# Middle_SEU.net
KiCad netlist of a schematic drawn in Altium Designer
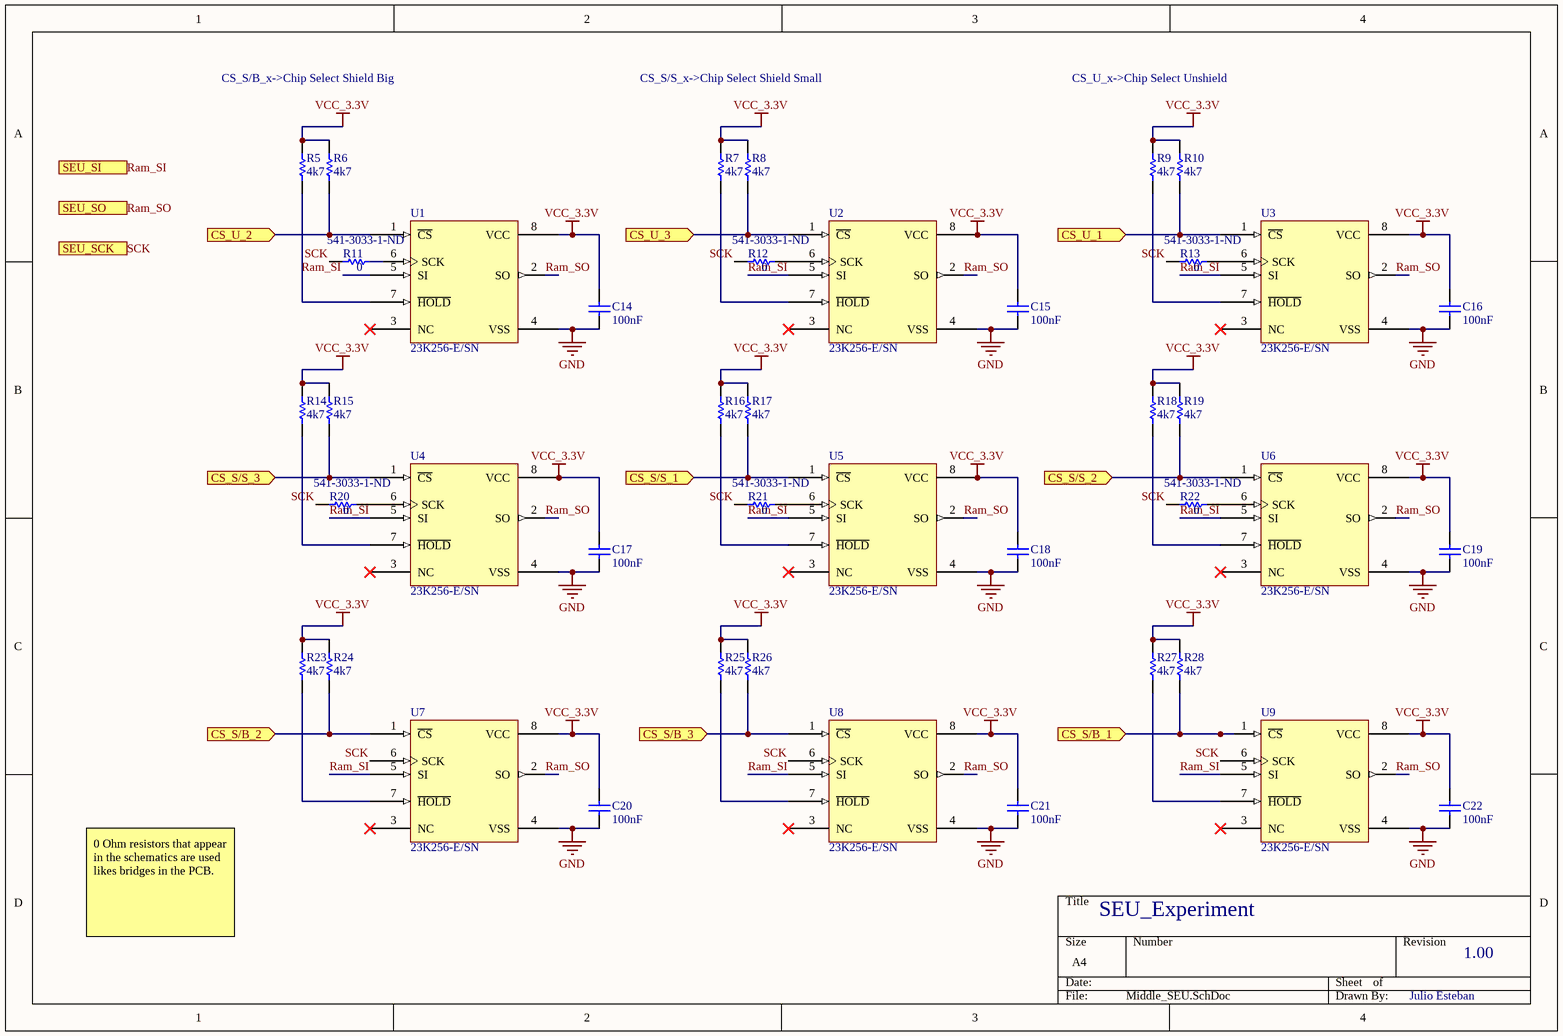
[diagram p0: Middle_SEU.SchDoc]

(export (version "E")
  (design (tool "Eeschema 10.0.6"))
  (components
    (comp (ref "C14")
      (value "100nF")
      (footprint "C1206")
      (description "1206 Capacitor")
      (libsource (lib "Middle_Symbols") (part "C1206"))
    )
    (comp (ref "C15")
      (value "100nF")
      (footprint "C1206")
      (description "1206 Capacitor")
      (libsource (lib "Middle_Symbols") (part "C1206"))
    )
    (comp (ref "C16")
      (value "100nF")
      (footprint "C1206")
      (description "1206 Capacitor")
      (libsource (lib "Middle_Symbols") (part "C1206"))
    )
    (comp (ref "C17")
      (value "100nF")
      (footprint "C1206")
      (description "1206 Capacitor")
      (libsource (lib "Middle_Symbols") (part "C1206"))
    )
    (comp (ref "C18")
      (value "100nF")
      (footprint "C1206")
      (description "1206 Capacitor")
      (libsource (lib "Middle_Symbols") (part "C1206"))
    )
    (comp (ref "C19")
      (value "100nF")
      (footprint "C1206")
      (description "1206 Capacitor")
      (libsource (lib "Middle_Symbols") (part "C1206"))
    )
    (comp (ref "C20")
      (value "100nF")
      (footprint "C1206")
      (description "1206 Capacitor")
      (libsource (lib "Middle_Symbols") (part "C1206"))
    )
    (comp (ref "C21")
      (value "100nF")
      (footprint "C1206")
      (description "1206 Capacitor")
      (libsource (lib "Middle_Symbols") (part "C1206"))
    )
    (comp (ref "C22")
      (value "100nF")
      (footprint "C1206")
      (description "1206 Capacitor")
      (libsource (lib "Middle_Symbols") (part "C1206"))
    )
    (comp (ref "R5")
      (value "4k7")
      (footprint "R1206")
      (description "1206 Resistor")
      (libsource (lib "Middle_Symbols") (part "R1206"))
    )
    (comp (ref "R6")
      (value "4k7")
      (footprint "R1206")
      (description "1206 Resistor")
      (libsource (lib "Middle_Symbols") (part "R1206"))
    )
    (comp (ref "R7")
      (value "4k7")
      (footprint "R1206")
      (description "1206 Resistor")
      (libsource (lib "Middle_Symbols") (part "R1206"))
    )
    (comp (ref "R8")
      (value "4k7")
      (footprint "R1206")
      (description "1206 Resistor")
      (libsource (lib "Middle_Symbols") (part "R1206"))
    )
    (comp (ref "R9")
      (value "4k7")
      (footprint "R1206")
      (description "1206 Resistor")
      (libsource (lib "Middle_Symbols") (part "R1206"))
    )
    (comp (ref "R10")
      (value "4k7")
      (footprint "R1206")
      (description "1206 Resistor")
      (libsource (lib "Middle_Symbols") (part "R1206"))
    )
    (comp (ref "R11")
      (value "0")
      (footprint "R1206")
      (description "1206 Resistor")
      (fields (field (name "SUPPLIER PART NUMBER 1") "541-3033-1-ND"))
      (libsource (lib "Middle_Symbols") (part "R1206"))
    )
    (comp (ref "R12")
      (value "0")
      (footprint "R1206")
      (description "1206 Resistor")
      (fields (field (name "SUPPLIER PART NUMBER 1") "541-3033-1-ND"))
      (libsource (lib "Middle_Symbols") (part "R1206"))
    )
    (comp (ref "R13")
      (value "0")
      (footprint "R1206")
      (description "1206 Resistor")
      (fields (field (name "SUPPLIER PART NUMBER 1") "541-3033-1-ND"))
      (libsource (lib "Middle_Symbols") (part "R1206"))
    )
    (comp (ref "R14")
      (value "4k7")
      (footprint "R1206")
      (description "1206 Resistor")
      (libsource (lib "Middle_Symbols") (part "R1206"))
    )
    (comp (ref "R15")
      (value "4k7")
      (footprint "R1206")
      (description "1206 Resistor")
      (libsource (lib "Middle_Symbols") (part "R1206"))
    )
    (comp (ref "R16")
      (value "4k7")
      (footprint "R1206")
      (description "1206 Resistor")
      (libsource (lib "Middle_Symbols") (part "R1206"))
    )
    (comp (ref "R17")
      (value "4k7")
      (footprint "R1206")
      (description "1206 Resistor")
      (libsource (lib "Middle_Symbols") (part "R1206"))
    )
    (comp (ref "R18")
      (value "4k7")
      (footprint "R1206")
      (description "1206 Resistor")
      (libsource (lib "Middle_Symbols") (part "R1206"))
    )
    (comp (ref "R19")
      (value "4k7")
      (footprint "R1206")
      (description "1206 Resistor")
      (libsource (lib "Middle_Symbols") (part "R1206"))
    )
    (comp (ref "R20")
      (value "0")
      (footprint "R1206")
      (description "1206 Resistor")
      (fields (field (name "SUPPLIER PART NUMBER 1") "541-3033-1-ND"))
      (libsource (lib "Middle_Symbols") (part "R1206"))
    )
    (comp (ref "R21")
      (value "0")
      (footprint "R1206")
      (description "1206 Resistor")
      (fields (field (name "SUPPLIER PART NUMBER 1") "541-3033-1-ND"))
      (libsource (lib "Middle_Symbols") (part "R1206"))
    )
    (comp (ref "R22")
      (value "0")
      (footprint "R1206")
      (description "1206 Resistor")
      (fields (field (name "SUPPLIER PART NUMBER 1") "541-3033-1-ND"))
      (libsource (lib "Middle_Symbols") (part "R1206"))
    )
    (comp (ref "R23")
      (value "4k7")
      (footprint "R1206")
      (description "1206 Resistor")
      (libsource (lib "Middle_Symbols") (part "R1206"))
    )
    (comp (ref "R24")
      (value "4k7")
      (footprint "R1206")
      (description "1206 Resistor")
      (libsource (lib "Middle_Symbols") (part "R1206"))
    )
    (comp (ref "R25")
      (value "4k7")
      (footprint "R1206")
      (description "1206 Resistor")
      (libsource (lib "Middle_Symbols") (part "R1206"))
    )
    (comp (ref "R26")
      (value "4k7")
      (footprint "R1206")
      (description "1206 Resistor")
      (libsource (lib "Middle_Symbols") (part "R1206"))
    )
    (comp (ref "R27")
      (value "4k7")
      (footprint "R1206")
      (description "1206 Resistor")
      (libsource (lib "Middle_Symbols") (part "R1206"))
    )
    (comp (ref "R28")
      (value "4k7")
      (footprint "R1206")
      (description "1206 Resistor")
      (libsource (lib "Middle_Symbols") (part "R1206"))
    )
    (comp (ref "U1")
      (value "23K256-E/SN")
      (footprint "SOIC-SN8_L")
      (description "256K, 32768x8-bit, 3.6V SPI Serial SRAM, 8-Pin SOIC 3.9mm, Extended Temperature")
      (fields (field (name "MANUFACTURER") "Microchip"))
      (libsource (lib "Schlib1") (part "23K256-E/SN"))
    )
    (comp (ref "U2")
      (value "23K256-E/SN")
      (footprint "SOIC-SN8_L")
      (description "256K, 32768x8-bit, 3.6V SPI Serial SRAM, 8-Pin SOIC 3.9mm, Extended Temperature")
      (fields (field (name "MANUFACTURER") "Microchip"))
      (libsource (lib "Schlib1") (part "23K256-E/SN"))
    )
    (comp (ref "U3")
      (value "23K256-E/SN")
      (footprint "SOIC-SN8_L")
      (description "256K, 32768x8-bit, 3.6V SPI Serial SRAM, 8-Pin SOIC 3.9mm, Extended Temperature")
      (fields (field (name "MANUFACTURER") "Microchip"))
      (libsource (lib "Schlib1") (part "23K256-E/SN"))
    )
    (comp (ref "U4")
      (value "23K256-E/SN")
      (footprint "SOIC-SN8_L")
      (description "256K, 32768x8-bit, 3.6V SPI Serial SRAM, 8-Pin SOIC 3.9mm, Extended Temperature")
      (fields (field (name "MANUFACTURER") "Microchip"))
      (libsource (lib "Schlib1") (part "23K256-E/SN"))
    )
    (comp (ref "U5")
      (value "23K256-E/SN")
      (footprint "SOIC-SN8_L")
      (description "256K, 32768x8-bit, 3.6V SPI Serial SRAM, 8-Pin SOIC 3.9mm, Extended Temperature")
      (fields (field (name "MANUFACTURER") "Microchip"))
      (libsource (lib "Schlib1") (part "23K256-E/SN"))
    )
    (comp (ref "U6")
      (value "23K256-E/SN")
      (footprint "SOIC-SN8_L")
      (description "256K, 32768x8-bit, 3.6V SPI Serial SRAM, 8-Pin SOIC 3.9mm, Extended Temperature")
      (fields (field (name "MANUFACTURER") "Microchip"))
      (libsource (lib "Schlib1") (part "23K256-E/SN"))
    )
    (comp (ref "U7")
      (value "23K256-E/SN")
      (footprint "SOIC-SN8_L")
      (description "256K, 32768x8-bit, 3.6V SPI Serial SRAM, 8-Pin SOIC 3.9mm, Extended Temperature")
      (fields (field (name "MANUFACTURER") "Microchip"))
      (libsource (lib "Schlib1") (part "23K256-E/SN"))
    )
    (comp (ref "U8")
      (value "23K256-E/SN")
      (footprint "SOIC-SN8_L")
      (description "256K, 32768x8-bit, 3.6V SPI Serial SRAM, 8-Pin SOIC 3.9mm, Extended Temperature")
      (fields (field (name "MANUFACTURER") "Microchip"))
      (libsource (lib "Schlib1") (part "23K256-E/SN"))
    )
    (comp (ref "U9")
      (value "23K256-E/SN")
      (footprint "SOIC-SN8_L")
      (description "256K, 32768x8-bit, 3.6V SPI Serial SRAM, 8-Pin SOIC 3.9mm, Extended Temperature")
      (fields (field (name "MANUFACTURER") "Microchip"))
      (libsource (lib "Schlib1") (part "23K256-E/SN"))
    )
  )
  (nets
    (net (code "1") (name "/CS_S{slash}B_1") (class "Default")
      (node (ref "R28") (pin "1") (pinfunction "1_1") (pintype "passive"))
      (node (ref "U9") (pin "1") (pinfunction "~{CS}_1") (pintype "input"))
    )
    (net (code "2") (name "/CS_S{slash}B_2") (class "Default")
      (node (ref "R24") (pin "1") (pinfunction "1_1") (pintype "passive"))
      (node (ref "U7") (pin "1") (pinfunction "~{CS}_1") (pintype "input"))
    )
    (net (code "3") (name "/CS_S{slash}B_3") (class "Default")
      (node (ref "R26") (pin "1") (pinfunction "1_1") (pintype "passive"))
      (node (ref "U8") (pin "1") (pinfunction "~{CS}_1") (pintype "input"))
    )
    (net (code "4") (name "/CS_S{slash}S_1") (class "Default")
      (node (ref "R17") (pin "1") (pinfunction "1_1") (pintype "passive"))
      (node (ref "U5") (pin "1") (pinfunction "~{CS}_1") (pintype "input"))
    )
    (net (code "5") (name "/CS_S{slash}S_2") (class "Default")
      (node (ref "R19") (pin "1") (pinfunction "1_1") (pintype "passive"))
      (node (ref "U6") (pin "1") (pinfunction "~{CS}_1") (pintype "input"))
    )
    (net (code "6") (name "/CS_S{slash}S_3") (class "Default")
      (node (ref "R15") (pin "1") (pinfunction "1_1") (pintype "passive"))
      (node (ref "U4") (pin "1") (pinfunction "~{CS}_1") (pintype "input"))
    )
    (net (code "7") (name "/CS_U_1") (class "Default")
      (node (ref "R10") (pin "1") (pinfunction "1_1") (pintype "passive"))
      (node (ref "U3") (pin "1") (pinfunction "~{CS}_1") (pintype "input"))
    )
    (net (code "8") (name "/CS_U_2") (class "Default")
      (node (ref "R6") (pin "1") (pinfunction "1_1") (pintype "passive"))
      (node (ref "U1") (pin "1") (pinfunction "~{CS}_1") (pintype "input"))
    )
    (net (code "9") (name "/CS_U_3") (class "Default")
      (node (ref "R8") (pin "1") (pinfunction "1_1") (pintype "passive"))
      (node (ref "U2") (pin "1") (pinfunction "~{CS}_1") (pintype "input"))
    )
    (net (code "10") (name "/Ram_SI") (class "Default")
      (node (ref "U1") (pin "5") (pinfunction "SI_5") (pintype "input"))
      (node (ref "U2") (pin "5") (pinfunction "SI_5") (pintype "input"))
      (node (ref "U3") (pin "5") (pinfunction "SI_5") (pintype "input"))
      (node (ref "U4") (pin "5") (pinfunction "SI_5") (pintype "input"))
      (node (ref "U5") (pin "5") (pinfunction "SI_5") (pintype "input"))
      (node (ref "U6") (pin "5") (pinfunction "SI_5") (pintype "input"))
      (node (ref "U7") (pin "5") (pinfunction "SI_5") (pintype "input"))
      (node (ref "U8") (pin "5") (pinfunction "SI_5") (pintype "input"))
      (node (ref "U9") (pin "5") (pinfunction "SI_5") (pintype "input"))
    )
    (net (code "11") (name "/Ram_SO") (class "Default")
      (node (ref "U1") (pin "2") (pinfunction "SO_2") (pintype "output"))
      (node (ref "U2") (pin "2") (pinfunction "SO_2") (pintype "output"))
      (node (ref "U3") (pin "2") (pinfunction "SO_2") (pintype "output"))
      (node (ref "U4") (pin "2") (pinfunction "SO_2") (pintype "output"))
      (node (ref "U5") (pin "2") (pinfunction "SO_2") (pintype "output"))
      (node (ref "U6") (pin "2") (pinfunction "SO_2") (pintype "output"))
      (node (ref "U7") (pin "2") (pinfunction "SO_2") (pintype "output"))
      (node (ref "U8") (pin "2") (pinfunction "SO_2") (pintype "output"))
      (node (ref "U9") (pin "2") (pinfunction "SO_2") (pintype "output"))
    )
    (net (code "12") (name "/SCK") (class "Default")
      (node (ref "R11") (pin "2") (pinfunction "2_2") (pintype "passive"))
      (node (ref "R12") (pin "2") (pinfunction "2_2") (pintype "passive"))
      (node (ref "R13") (pin "2") (pinfunction "2_2") (pintype "passive"))
      (node (ref "R20") (pin "2") (pinfunction "2_2") (pintype "passive"))
      (node (ref "R21") (pin "2") (pinfunction "2_2") (pintype "passive"))
      (node (ref "R22") (pin "2") (pinfunction "2_2") (pintype "passive"))
      (node (ref "U7") (pin "6") (pinfunction "SCK_6") (pintype "input"))
      (node (ref "U8") (pin "6") (pinfunction "SCK_6") (pintype "input"))
      (node (ref "U9") (pin "6") (pinfunction "SCK_6") (pintype "input"))
    )
    (net (code "13") (name "GND") (class "Default")
      (node (ref "C14") (pin "1") (pinfunction "1_1") (pintype "passive"))
      (node (ref "C15") (pin "1") (pinfunction "1_1") (pintype "passive"))
      (node (ref "C16") (pin "1") (pinfunction "1_1") (pintype "passive"))
      (node (ref "C17") (pin "1") (pinfunction "1_1") (pintype "passive"))
      (node (ref "C18") (pin "1") (pinfunction "1_1") (pintype "passive"))
      (node (ref "C19") (pin "1") (pinfunction "1_1") (pintype "passive"))
      (node (ref "C20") (pin "1") (pinfunction "1_1") (pintype "passive"))
      (node (ref "C21") (pin "1") (pinfunction "1_1") (pintype "passive"))
      (node (ref "C22") (pin "1") (pinfunction "1_1") (pintype "passive"))
      (node (ref "U1") (pin "4") (pinfunction "VSS_4") (pintype "power_in"))
      (node (ref "U2") (pin "4") (pinfunction "VSS_4") (pintype "power_in"))
      (node (ref "U3") (pin "4") (pinfunction "VSS_4") (pintype "power_in"))
      (node (ref "U4") (pin "4") (pinfunction "VSS_4") (pintype "power_in"))
      (node (ref "U5") (pin "4") (pinfunction "VSS_4") (pintype "power_in"))
      (node (ref "U6") (pin "4") (pinfunction "VSS_4") (pintype "power_in"))
      (node (ref "U7") (pin "4") (pinfunction "VSS_4") (pintype "power_in"))
      (node (ref "U8") (pin "4") (pinfunction "VSS_4") (pintype "power_in"))
      (node (ref "U9") (pin "4") (pinfunction "VSS_4") (pintype "power_in"))
    )
    (net (code "14") (name "Net-(U1-SCK)") (class "Default")
      (node (ref "R11") (pin "1") (pinfunction "1_1") (pintype "passive"))
      (node (ref "U1") (pin "6") (pinfunction "SCK_6") (pintype "input"))
    )
    (net (code "15") (name "Net-(U1-~{HOLD})") (class "Default")
      (node (ref "R5") (pin "1") (pinfunction "1_1") (pintype "passive"))
      (node (ref "U1") (pin "7") (pinfunction "~{HOLD}_7") (pintype "input"))
    )
    (net (code "16") (name "Net-(U2-SCK)") (class "Default")
      (node (ref "R12") (pin "1") (pinfunction "1_1") (pintype "passive"))
      (node (ref "U2") (pin "6") (pinfunction "SCK_6") (pintype "input"))
    )
    (net (code "17") (name "Net-(U2-~{HOLD})") (class "Default")
      (node (ref "R7") (pin "1") (pinfunction "1_1") (pintype "passive"))
      (node (ref "U2") (pin "7") (pinfunction "~{HOLD}_7") (pintype "input"))
    )
    (net (code "18") (name "Net-(U3-SCK)") (class "Default")
      (node (ref "R13") (pin "1") (pinfunction "1_1") (pintype "passive"))
      (node (ref "U3") (pin "6") (pinfunction "SCK_6") (pintype "input"))
    )
    (net (code "19") (name "Net-(U3-~{HOLD})") (class "Default")
      (node (ref "R9") (pin "1") (pinfunction "1_1") (pintype "passive"))
      (node (ref "U3") (pin "7") (pinfunction "~{HOLD}_7") (pintype "input"))
    )
    (net (code "20") (name "Net-(U4-SCK)") (class "Default")
      (node (ref "R20") (pin "1") (pinfunction "1_1") (pintype "passive"))
      (node (ref "U4") (pin "6") (pinfunction "SCK_6") (pintype "input"))
    )
    (net (code "21") (name "Net-(U4-~{HOLD})") (class "Default")
      (node (ref "R14") (pin "1") (pinfunction "1_1") (pintype "passive"))
      (node (ref "U4") (pin "7") (pinfunction "~{HOLD}_7") (pintype "input"))
    )
    (net (code "22") (name "Net-(U5-SCK)") (class "Default")
      (node (ref "R21") (pin "1") (pinfunction "1_1") (pintype "passive"))
      (node (ref "U5") (pin "6") (pinfunction "SCK_6") (pintype "input"))
    )
    (net (code "23") (name "Net-(U5-~{HOLD})") (class "Default")
      (node (ref "R16") (pin "1") (pinfunction "1_1") (pintype "passive"))
      (node (ref "U5") (pin "7") (pinfunction "~{HOLD}_7") (pintype "input"))
    )
    (net (code "24") (name "Net-(U6-SCK)") (class "Default")
      (node (ref "R22") (pin "1") (pinfunction "1_1") (pintype "passive"))
      (node (ref "U6") (pin "6") (pinfunction "SCK_6") (pintype "input"))
    )
    (net (code "25") (name "Net-(U6-~{HOLD})") (class "Default")
      (node (ref "R18") (pin "1") (pinfunction "1_1") (pintype "passive"))
      (node (ref "U6") (pin "7") (pinfunction "~{HOLD}_7") (pintype "input"))
    )
    (net (code "26") (name "Net-(U7-~{HOLD})") (class "Default")
      (node (ref "R23") (pin "1") (pinfunction "1_1") (pintype "passive"))
      (node (ref "U7") (pin "7") (pinfunction "~{HOLD}_7") (pintype "input"))
    )
    (net (code "27") (name "Net-(U8-~{HOLD})") (class "Default")
      (node (ref "R25") (pin "1") (pinfunction "1_1") (pintype "passive"))
      (node (ref "U8") (pin "7") (pinfunction "~{HOLD}_7") (pintype "input"))
    )
    (net (code "28") (name "Net-(U9-~{HOLD})") (class "Default")
      (node (ref "R27") (pin "1") (pinfunction "1_1") (pintype "passive"))
      (node (ref "U9") (pin "7") (pinfunction "~{HOLD}_7") (pintype "input"))
    )
    (net (code "29") (name "VCC_3.3V") (class "Default")
      (node (ref "C14") (pin "2") (pinfunction "2_2") (pintype "passive"))
      (node (ref "C15") (pin "2") (pinfunction "2_2") (pintype "passive"))
      (node (ref "C16") (pin "2") (pinfunction "2_2") (pintype "passive"))
      (node (ref "C17") (pin "2") (pinfunction "2_2") (pintype "passive"))
      (node (ref "C18") (pin "2") (pinfunction "2_2") (pintype "passive"))
      (node (ref "C19") (pin "2") (pinfunction "2_2") (pintype "passive"))
      (node (ref "C20") (pin "2") (pinfunction "2_2") (pintype "passive"))
      (node (ref "C21") (pin "2") (pinfunction "2_2") (pintype "passive"))
      (node (ref "C22") (pin "2") (pinfunction "2_2") (pintype "passive"))
      (node (ref "R10") (pin "2") (pinfunction "2_2") (pintype "passive"))
      (node (ref "R14") (pin "2") (pinfunction "2_2") (pintype "passive"))
      (node (ref "R15") (pin "2") (pinfunction "2_2") (pintype "passive"))
      (node (ref "R16") (pin "2") (pinfunction "2_2") (pintype "passive"))
      (node (ref "R17") (pin "2") (pinfunction "2_2") (pintype "passive"))
      (node (ref "R18") (pin "2") (pinfunction "2_2") (pintype "passive"))
      (node (ref "R19") (pin "2") (pinfunction "2_2") (pintype "passive"))
      (node (ref "R23") (pin "2") (pinfunction "2_2") (pintype "passive"))
      (node (ref "R24") (pin "2") (pinfunction "2_2") (pintype "passive"))
      (node (ref "R25") (pin "2") (pinfunction "2_2") (pintype "passive"))
      (node (ref "R26") (pin "2") (pinfunction "2_2") (pintype "passive"))
      (node (ref "R27") (pin "2") (pinfunction "2_2") (pintype "passive"))
      (node (ref "R28") (pin "2") (pinfunction "2_2") (pintype "passive"))
      (node (ref "R5") (pin "2") (pinfunction "2_2") (pintype "passive"))
      (node (ref "R6") (pin "2") (pinfunction "2_2") (pintype "passive"))
      (node (ref "R7") (pin "2") (pinfunction "2_2") (pintype "passive"))
      (node (ref "R8") (pin "2") (pinfunction "2_2") (pintype "passive"))
      (node (ref "R9") (pin "2") (pinfunction "2_2") (pintype "passive"))
      (node (ref "U1") (pin "8") (pinfunction "VCC_8") (pintype "power_in"))
      (node (ref "U2") (pin "8") (pinfunction "VCC_8") (pintype "power_in"))
      (node (ref "U3") (pin "8") (pinfunction "VCC_8") (pintype "power_in"))
      (node (ref "U4") (pin "8") (pinfunction "VCC_8") (pintype "power_in"))
      (node (ref "U5") (pin "8") (pinfunction "VCC_8") (pintype "power_in"))
      (node (ref "U6") (pin "8") (pinfunction "VCC_8") (pintype "power_in"))
      (node (ref "U7") (pin "8") (pinfunction "VCC_8") (pintype "power_in"))
      (node (ref "U8") (pin "8") (pinfunction "VCC_8") (pintype "power_in"))
      (node (ref "U9") (pin "8") (pinfunction "VCC_8") (pintype "power_in"))
    )
    (net (code "30") (name "unconnected-(U1-NC-Pad3)") (class "Default")
      (node (ref "U1") (pin "3") (pinfunction "NC_3") (pintype "passive+no_connect"))
    )
    (net (code "31") (name "unconnected-(U2-NC-Pad3)") (class "Default")
      (node (ref "U2") (pin "3") (pinfunction "NC_3") (pintype "passive+no_connect"))
    )
    (net (code "32") (name "unconnected-(U3-NC-Pad3)") (class "Default")
      (node (ref "U3") (pin "3") (pinfunction "NC_3") (pintype "passive+no_connect"))
    )
    (net (code "33") (name "unconnected-(U4-NC-Pad3)") (class "Default")
      (node (ref "U4") (pin "3") (pinfunction "NC_3") (pintype "passive+no_connect"))
    )
    (net (code "34") (name "unconnected-(U5-NC-Pad3)") (class "Default")
      (node (ref "U5") (pin "3") (pinfunction "NC_3") (pintype "passive+no_connect"))
    )
    (net (code "35") (name "unconnected-(U6-NC-Pad3)") (class "Default")
      (node (ref "U6") (pin "3") (pinfunction "NC_3") (pintype "passive+no_connect"))
    )
    (net (code "36") (name "unconnected-(U7-NC-Pad3)") (class "Default")
      (node (ref "U7") (pin "3") (pinfunction "NC_3") (pintype "passive+no_connect"))
    )
    (net (code "37") (name "unconnected-(U8-NC-Pad3)") (class "Default")
      (node (ref "U8") (pin "3") (pinfunction "NC_3") (pintype "passive+no_connect"))
    )
    (net (code "38") (name "unconnected-(U9-NC-Pad3)") (class "Default")
      (node (ref "U9") (pin "3") (pinfunction "NC_3") (pintype "passive+no_connect"))
    )
  )
)
